# TEC_controller.net
KiCad netlist of a schematic drawn in Altium Designer
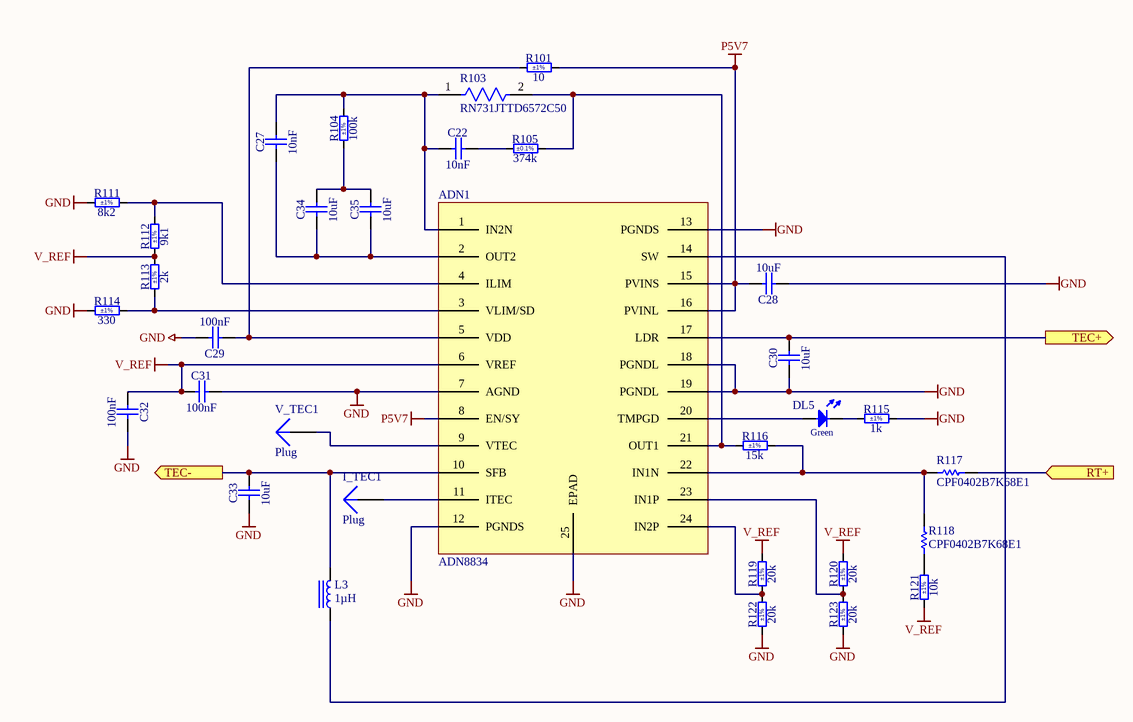
[diagram p0: TEC_controller.SchDoc]

(export (version "E")
  (design (tool "Eeschema 10.0.6"))
  (components
    (comp (ref "ADN1")
      (value "ADN8834")
      (footprint "SMSC QFN-24 4x4MM")
      (description "TEC")
      (libsource (lib "VCSEL_Driver_Lib") (part "ADN8834"))
    )
    (comp (ref "C22")
      (value "10nF")
      (footprint "CAPC1005X55N")
      (description "Non-polarised capacitor")
      (fields
        (field (name "PART NUMBER") "CC0402_10NF_16V_10%_X7R")
        (field (name "VOLTAGE") "16V")
        (field (name "AUTHOR") "CERN DEM JLC")
      )
      (libsource (lib "Capacitors") (part "Capacitor - non polarized"))
    )
    (comp (ref "C27")
      (value "10nF")
      (footprint "CAPC1005X55N")
      (description "Non-polarised capacitor")
      (fields
        (field (name "PART NUMBER") "CC0402_10NF_16V_10%_X7R")
        (field (name "VOLTAGE") "16V")
        (field (name "AUTHOR") "CERN DEM JLC")
      )
      (libsource (lib "Capacitors") (part "Capacitor - non polarized"))
    )
    (comp (ref "C28")
      (value "10uF")
      (footprint "CAPC1005X70N")
      (description "Non-polarised capacitor")
      (fields
        (field (name "PART NUMBER") "CC0402_10UF_6.3V_20%_X5R")
        (field (name "VOLTAGE") "6.3V")
        (field (name "AUTHOR") "CERN DEM JLC")
      )
      (libsource (lib "Capacitors") (part "Capacitor - non polarized"))
    )
    (comp (ref "C29")
      (value "100nF")
      (footprint "CAPC1005X55N")
      (description "Non-polarised capacitor")
      (fields
        (field (name "PART NUMBER") "CC0402_100NF_16V_10%_X7R")
        (field (name "VOLTAGE") "16V")
        (field (name "AUTHOR") "CERN DEM JLC")
      )
      (libsource (lib "Capacitors") (part "Capacitor - non polarized"))
    )
    (comp (ref "C30")
      (value "10uF")
      (footprint "CAPC1005X70N")
      (description "Non-polarised capacitor")
      (fields
        (field (name "PART NUMBER") "CC0402_10UF_6.3V_20%_X5R")
        (field (name "VOLTAGE") "6.3V")
        (field (name "AUTHOR") "CERN DEM JLC")
      )
      (libsource (lib "Capacitors") (part "Capacitor - non polarized"))
    )
    (comp (ref "C31")
      (value "100nF")
      (footprint "CAPC1005X55N")
      (description "Non-polarised capacitor")
      (fields
        (field (name "PART NUMBER") "CC0402_100NF_16V_10%_X7R")
        (field (name "VOLTAGE") "16V")
        (field (name "AUTHOR") "CERN DEM JLC")
      )
      (libsource (lib "Capacitors") (part "Capacitor - non polarized"))
    )
    (comp (ref "C32")
      (value "100nF")
      (footprint "CAPC1005X55N")
      (description "Non-polarised capacitor")
      (fields
        (field (name "PART NUMBER") "CC0402_100NF_16V_10%_X7R")
        (field (name "VOLTAGE") "16V")
        (field (name "AUTHOR") "CERN DEM JLC")
      )
      (libsource (lib "Capacitors") (part "Capacitor - non polarized"))
    )
    (comp (ref "C33")
      (value "10uF")
      (footprint "CAPC1005X70N")
      (description "Non-polarised capacitor")
      (fields
        (field (name "PART NUMBER") "CC0402_10UF_6.3V_20%_X5R")
        (field (name "VOLTAGE") "6.3V")
        (field (name "AUTHOR") "CERN DEM JLC")
      )
      (libsource (lib "Capacitors") (part "Capacitor - non polarized"))
    )
    (comp (ref "C34")
      (value "10uF")
      (footprint "CAPC1608X80N")
      (description "Non-polarised capacitor")
      (fields
        (field (name "PART NUMBER") "CC0603_10UF_16V_20%_X5R")
        (field (name "VOLTAGE") "16V")
        (field (name "AUTHOR") "CERN DEM MR")
      )
      (libsource (lib "Capacitors") (part "Capacitor - non polarized"))
    )
    (comp (ref "C35")
      (value "10uF")
      (footprint "CAPC1608X80N")
      (description "Non-polarised capacitor")
      (fields
        (field (name "PART NUMBER") "CC0603_10UF_16V_20%_X5R")
        (field (name "VOLTAGE") "16V")
        (field (name "AUTHOR") "CERN DEM MR")
      )
      (libsource (lib "Capacitors") (part "Capacitor - non polarized"))
    )
    (comp (ref "DL5")
      (value "Green")
      (footprint "LED_OSRAM_LGL29K")
      (description "LED Green 1C 2A")
      (fields
        (field (name "PART NUMBER") "LED_OSRAM_LG L29K-G2J1-24-Z")
        (field (name "MANUFACTURER") "OSRAM")
        (field (name "AUTHOR") "CERN DEM JLC")
      )
      (libsource (lib "ICs And Semiconductors") (part "LED Green 1C 2A"))
    )
    (comp (ref "I_TEC1")
      (value "Plug")
      (footprint "PIN1")
      (fields (field (name "PUBLISHER") "Altium Limited"))
      (libsource (lib "Miscellaneous Connectors") (part "Plug"))
    )
    (comp (ref "L3")
      (value "1µH")
      (footprint "IND 0806_2016")
      (description "FIXED IND 1UH 1.7A 107MOHM SMD")
      (fields
        (field (name "PART NUMBER") "SDED20161T-1R0MS")
        (field (name "MANUFACTURER") "Delta Electronics/Cyntec")
      )
      (libsource (lib "Celestial Altium Library - altium_library") (part "Inductor"))
    )
    (comp (ref "R101")
      (value "10")
      (footprint "RESC1005X40N")
      (description "Resistor - 1%")
      (fields
        (field (name "TOLERANCE") "±1%")
        (field (name "PART NUMBER") "R0402_10R_1%_0.0625W_200PPM")
        (field (name "POWER") "0.0625W")
        (field (name "AUTHOR") "CERN DEM JLC")
      )
      (libsource (lib "Resistors") (part "Resistor - 1%"))
    )
    (comp (ref "R103")
      (value "RN731JTTD6572C50")
      (footprint "FP-RN731J-IPC_B")
      (description "65.7kΩ ±0.25% 0.063W, 1/16W Chip Resistor 0603 (1608 Metric) Moisture Resistant Thin Film")
      (fields (field (name "TOLERANCE") "0.25%"))
      (libsource (lib "Altium Content Vault") (part "1029c3af85768c4190bb7ad29bc67b5"))
    )
    (comp (ref "R104")
      (value "100k")
      (footprint "RESC1005X40N")
      (description "Resistor - 1%")
      (fields
        (field (name "TOLERANCE") "±1%")
        (field (name "PART NUMBER") "R0402_100K_1%_0.0625W_100PPM")
        (field (name "POWER") "0.0625W")
        (field (name "AUTHOR") "CERN DEM JLC")
      )
      (libsource (lib "Resistors") (part "Resistor - 1%"))
    )
    (comp (ref "R105")
      (value "374k")
      (footprint "RESC1608X55N")
      (description "Resistor - 0.1%")
      (fields
        (field (name "TOLERANCE") "±0.1%")
        (field (name "PART NUMBER") "R0603_374K_0.1%_0.063W_25PPM")
        (field (name "POWER") "0.063W")
        (field (name "AUTHOR") "CERN DEM JLC")
      )
      (libsource (lib "Resistors") (part "Resistor - 0.1%"))
    )
    (comp (ref "R111")
      (value "8k2")
      (footprint "RESC1005X40N")
      (description "Resistor - 1%")
      (fields
        (field (name "TOLERANCE") "±1%")
        (field (name "PART NUMBER") "R0402_8K2_1%_0.0625W_100PPM")
        (field (name "POWER") "0.0625W")
        (field (name "AUTHOR") "CERN DEM JLC")
      )
      (libsource (lib "Resistors") (part "Resistor - 1%"))
    )
    (comp (ref "R112")
      (value "9k1")
      (footprint "RESC1005X40N")
      (description "Resistor - 1%")
      (fields
        (field (name "TOLERANCE") "±1%")
        (field (name "PART NUMBER") "R0402_9K1_1%_0.0625W_100PPM")
        (field (name "POWER") "0.0625W")
        (field (name "AUTHOR") "CERN DEM JLC")
      )
      (libsource (lib "Resistors") (part "Resistor - 1%"))
    )
    (comp (ref "R113")
      (value "2k")
      (footprint "RESC1005X40N")
      (description "Resistor - 1%")
      (fields
        (field (name "TOLERANCE") "±1%")
        (field (name "PART NUMBER") "R0402_2K_1%_0.0625W_100PPM")
        (field (name "POWER") "0.0625W")
        (field (name "AUTHOR") "CERN DEM JLC")
      )
      (libsource (lib "Resistors") (part "Resistor - 1%"))
    )
    (comp (ref "R114")
      (value "330")
      (footprint "RESC1005X40N")
      (description "Resistor - 1%")
      (fields
        (field (name "TOLERANCE") "±1%")
        (field (name "PART NUMBER") "R0402_330R_1%_0.0625W_100PPM")
        (field (name "POWER") "0.0625W")
        (field (name "AUTHOR") "CERN DEM JLC")
      )
      (libsource (lib "Resistors") (part "Resistor - 1%"))
    )
    (comp (ref "R115")
      (value "1k")
      (footprint "RESC1005X40N")
      (description "Resistor - 1%")
      (fields
        (field (name "TOLERANCE") "±1%")
        (field (name "PART NUMBER") "R0402_1K_1%_0.0625W_100PPM")
        (field (name "POWER") "0.0625W")
        (field (name "AUTHOR") "CERN DEM JLC")
      )
      (libsource (lib "Resistors") (part "Resistor - 1%"))
    )
    (comp (ref "R116")
      (value "15k")
      (footprint "RESC1005X40N")
      (description "Resistor - 1%")
      (fields
        (field (name "TOLERANCE") "±1%")
        (field (name "PART NUMBER") "R0402_15K_1%_0.0625W_100PPM")
        (field (name "POWER") "0.0625W")
        (field (name "AUTHOR") "CERN DEM JMW")
      )
      (libsource (lib "Resistors") (part "Resistor - 1%"))
    )
    (comp (ref "R117")
      (value "CPF0402B7K68E1")
      (footprint "RESC1005X35X20NL05T10")
      (fields (field (name "MANUFACTURER") "TE Connectivity / AMP"))
      (libsource (lib "Altium Content Vault") (part "RES"))
    )
    (comp (ref "R118")
      (value "CPF0402B7K68E1")
      (footprint "RESC1005X35X20NL05T10")
      (fields (field (name "MANUFACTURER") "TE Connectivity / AMP"))
      (libsource (lib "Altium Content Vault") (part "RES"))
    )
    (comp (ref "R119")
      (value "20k")
      (footprint "RESC1005X40N")
      (description "Resistor - 1%")
      (fields
        (field (name "TOLERANCE") "±1%")
        (field (name "PART NUMBER") "R0402_20K_1%_0.0625W_100PPM")
        (field (name "POWER") "0.0625W")
        (field (name "AUTHOR") "CERN DEM JLC")
      )
      (libsource (lib "Resistors") (part "Resistor - 1%"))
    )
    (comp (ref "R120")
      (value "20k")
      (footprint "RESC1005X40N")
      (description "Resistor - 1%")
      (fields
        (field (name "TOLERANCE") "±1%")
        (field (name "PART NUMBER") "R0402_20K_1%_0.0625W_100PPM")
        (field (name "POWER") "0.0625W")
        (field (name "AUTHOR") "CERN DEM JLC")
      )
      (libsource (lib "Resistors") (part "Resistor - 1%"))
    )
    (comp (ref "R121")
      (value "10k")
      (footprint "RESC1005X40N")
      (description "Resistor - 1%")
      (fields
        (field (name "TOLERANCE") "±1%")
        (field (name "PART NUMBER") "R0402_10K_1%_0.0625W_100PPM")
        (field (name "POWER") "0.0625W")
        (field (name "AUTHOR") "CERN DEM JLC")
      )
      (libsource (lib "Resistors") (part "Resistor - 1%"))
    )
    (comp (ref "R122")
      (value "20k")
      (footprint "RESC1005X40N")
      (description "Resistor - 1%")
      (fields
        (field (name "TOLERANCE") "±1%")
        (field (name "PART NUMBER") "R0402_20K_1%_0.0625W_100PPM")
        (field (name "POWER") "0.0625W")
        (field (name "AUTHOR") "CERN DEM JLC")
      )
      (libsource (lib "Resistors") (part "Resistor - 1%"))
    )
    (comp (ref "R123")
      (value "20k")
      (footprint "RESC1005X40N")
      (description "Resistor - 1%")
      (fields
        (field (name "TOLERANCE") "±1%")
        (field (name "PART NUMBER") "R0402_20K_1%_0.0625W_100PPM")
        (field (name "POWER") "0.0625W")
        (field (name "AUTHOR") "CERN DEM JLC")
      )
      (libsource (lib "Resistors") (part "Resistor - 1%"))
    )
    (comp (ref "V_TEC1")
      (value "Plug")
      (footprint "PIN1")
      (fields (field (name "PUBLISHER") "Altium Limited"))
      (libsource (lib "Miscellaneous Connectors") (part "Plug"))
    )
  )
  (nets
    (net (code "1") (name "/RT+") (class "Default")
      (node (ref "R117") (pin "2") (pinfunction "2_2") (pintype "passive"))
    )
    (net (code "2") (name "/TEC+") (class "Default")
      (node (ref "ADN1") (pin "17") (pinfunction "LDR_17") (pintype "passive"))
      (node (ref "C30") (pin "2") (pinfunction "2_2") (pintype "passive"))
    )
    (net (code "3") (name "/TEC-") (class "Default")
      (node (ref "ADN1") (pin "10") (pinfunction "SFB_10") (pintype "passive"))
      (node (ref "C33") (pin "2") (pinfunction "2_2") (pintype "passive"))
      (node (ref "L3") (pin "2") (pinfunction "2_2") (pintype "passive"))
    )
    (net (code "4") (name "GND") (class "Default")
      (node (ref "ADN1") (pin "12") (pinfunction "PGNDS_12") (pintype "passive"))
      (node (ref "ADN1") (pin "13") (pinfunction "PGNDS_13") (pintype "passive"))
      (node (ref "ADN1") (pin "18") (pinfunction "PGNDL_18") (pintype "passive"))
      (node (ref "ADN1") (pin "19") (pinfunction "PGNDL_19") (pintype "passive"))
      (node (ref "ADN1") (pin "25") (pinfunction "EPAD_25") (pintype "passive"))
      (node (ref "ADN1") (pin "7") (pinfunction "AGND_7") (pintype "passive"))
      (node (ref "C28") (pin "1") (pinfunction "1_1") (pintype "passive"))
      (node (ref "C29") (pin "2") (pinfunction "2_2") (pintype "passive"))
      (node (ref "C30") (pin "1") (pinfunction "1_1") (pintype "passive"))
      (node (ref "C31") (pin "2") (pinfunction "2_2") (pintype "passive"))
      (node (ref "C32") (pin "2") (pinfunction "2_2") (pintype "passive"))
      (node (ref "C33") (pin "1") (pinfunction "1_1") (pintype "passive"))
      (node (ref "R111") (pin "1") (pinfunction "1_1") (pintype "passive"))
      (node (ref "R114") (pin "1") (pinfunction "1_1") (pintype "passive"))
      (node (ref "R115") (pin "2") (pinfunction "2_2") (pintype "passive"))
      (node (ref "R122") (pin "1") (pinfunction "1_1") (pintype "passive"))
      (node (ref "R123") (pin "1") (pinfunction "1_1") (pintype "passive"))
    )
    (net (code "5") (name "Net-(ADN1-ILIM)") (class "Default")
      (node (ref "ADN1") (pin "4") (pinfunction "ILIM_4") (pintype "passive"))
      (node (ref "R111") (pin "2") (pinfunction "2_2") (pintype "passive"))
      (node (ref "R112") (pin "2") (pinfunction "2_2") (pintype "passive"))
    )
    (net (code "6") (name "Net-(ADN1-IN1N)") (class "Default")
      (node (ref "ADN1") (pin "22") (pinfunction "IN1N_22") (pintype "passive"))
      (node (ref "R116") (pin "2") (pinfunction "2_2") (pintype "passive"))
      (node (ref "R117") (pin "1") (pinfunction "1_1") (pintype "passive"))
      (node (ref "R118") (pin "2") (pinfunction "2_2") (pintype "passive"))
    )
    (net (code "7") (name "Net-(ADN1-IN1P)") (class "Default")
      (node (ref "ADN1") (pin "23") (pinfunction "IN1P_23") (pintype "passive"))
      (node (ref "R120") (pin "1") (pinfunction "1_1") (pintype "passive"))
      (node (ref "R123") (pin "2") (pinfunction "2_2") (pintype "passive"))
    )
    (net (code "8") (name "Net-(ADN1-IN2N)") (class "Default")
      (node (ref "ADN1") (pin "1") (pinfunction "IN2N_1") (pintype "passive"))
      (node (ref "C22") (pin "1") (pinfunction "1_1") (pintype "passive"))
      (node (ref "C27") (pin "2") (pinfunction "2_2") (pintype "passive"))
      (node (ref "R103") (pin "1") (pinfunction "1_1") (pintype "passive"))
      (node (ref "R104") (pin "2") (pinfunction "2_2") (pintype "passive"))
    )
    (net (code "9") (name "Net-(ADN1-IN2P)") (class "Default")
      (node (ref "ADN1") (pin "24") (pinfunction "IN2P_24") (pintype "passive"))
      (node (ref "R119") (pin "1") (pinfunction "1_1") (pintype "passive"))
      (node (ref "R122") (pin "2") (pinfunction "2_2") (pintype "passive"))
    )
    (net (code "10") (name "Net-(ADN1-ITEC)") (class "Default")
      (node (ref "ADN1") (pin "11") (pinfunction "ITEC_11") (pintype "passive"))
      (node (ref "I_TEC1") (pin "1") (pinfunction "1_1") (pintype "passive"))
    )
    (net (code "11") (name "Net-(ADN1-OUT1)") (class "Default")
      (node (ref "ADN1") (pin "21") (pinfunction "OUT1_21") (pintype "passive"))
      (node (ref "R103") (pin "2") (pinfunction "2_2") (pintype "passive"))
      (node (ref "R105") (pin "2") (pinfunction "2_2") (pintype "passive"))
      (node (ref "R116") (pin "1") (pinfunction "1_1") (pintype "passive"))
    )
    (net (code "12") (name "Net-(ADN1-OUT2)") (class "Default")
      (node (ref "ADN1") (pin "2") (pinfunction "OUT2_2") (pintype "passive"))
      (node (ref "C27") (pin "1") (pinfunction "1_1") (pintype "passive"))
      (node (ref "C34") (pin "1") (pinfunction "1_1") (pintype "passive"))
      (node (ref "C35") (pin "1") (pinfunction "1_1") (pintype "passive"))
    )
    (net (code "13") (name "Net-(ADN1-SW)") (class "Default")
      (node (ref "ADN1") (pin "14") (pinfunction "SW_14") (pintype "passive"))
      (node (ref "L3") (pin "1") (pinfunction "1_1") (pintype "passive"))
    )
    (net (code "14") (name "Net-(ADN1-TMPGD)") (class "Default")
      (node (ref "ADN1") (pin "20") (pinfunction "TMPGD_20") (pintype "passive"))
      (node (ref "DL5") (pin "2") (pinfunction "A_2") (pintype "passive"))
    )
    (net (code "15") (name "Net-(ADN1-VDD)") (class "Default")
      (node (ref "ADN1") (pin "5") (pinfunction "VDD_5") (pintype "passive"))
      (node (ref "C29") (pin "1") (pinfunction "1_1") (pintype "passive"))
      (node (ref "R101") (pin "1") (pinfunction "1_1") (pintype "passive"))
    )
    (net (code "16") (name "Net-(ADN1-VLIM{slash}SD)") (class "Default")
      (node (ref "ADN1") (pin "3") (pinfunction "VLIM/SD_3") (pintype "passive"))
      (node (ref "R113") (pin "1") (pinfunction "1_1") (pintype "passive"))
      (node (ref "R114") (pin "2") (pinfunction "2_2") (pintype "passive"))
    )
    (net (code "17") (name "Net-(ADN1-VTEC)") (class "Default")
      (node (ref "ADN1") (pin "9") (pinfunction "VTEC_9") (pintype "passive"))
      (node (ref "V_TEC1") (pin "1") (pinfunction "1_1") (pintype "passive"))
    )
    (net (code "18") (name "Net-(C22-Pad2)") (class "Default")
      (node (ref "C22") (pin "2") (pinfunction "2_2") (pintype "passive"))
      (node (ref "R105") (pin "1") (pinfunction "1_1") (pintype "passive"))
    )
    (net (code "19") (name "Net-(C34-Pad2)") (class "Default")
      (node (ref "C34") (pin "2") (pinfunction "2_2") (pintype "passive"))
      (node (ref "C35") (pin "2") (pinfunction "2_2") (pintype "passive"))
      (node (ref "R104") (pin "1") (pinfunction "1_1") (pintype "passive"))
    )
    (net (code "20") (name "Net-(DL5-C)") (class "Default")
      (node (ref "DL5") (pin "1") (pinfunction "C_1") (pintype "passive"))
      (node (ref "R115") (pin "1") (pinfunction "1_1") (pintype "passive"))
    )
    (net (code "21") (name "Net-(R118-Pad1)") (class "Default")
      (node (ref "R118") (pin "1") (pinfunction "1_1") (pintype "passive"))
      (node (ref "R121") (pin "2") (pinfunction "2_2") (pintype "passive"))
    )
    (net (code "22") (name "P5V7") (class "Default")
      (node (ref "ADN1") (pin "15") (pinfunction "PVINS_15") (pintype "passive"))
      (node (ref "ADN1") (pin "16") (pinfunction "PVINL_16") (pintype "passive"))
      (node (ref "ADN1") (pin "8") (pinfunction "EN/SY_8") (pintype "passive"))
      (node (ref "C28") (pin "2") (pinfunction "2_2") (pintype "passive"))
      (node (ref "R101") (pin "2") (pinfunction "2_2") (pintype "passive"))
    )
    (net (code "23") (name "V_REF") (class "Default")
      (node (ref "ADN1") (pin "6") (pinfunction "VREF_6") (pintype "passive"))
      (node (ref "C31") (pin "1") (pinfunction "1_1") (pintype "passive"))
      (node (ref "C32") (pin "1") (pinfunction "1_1") (pintype "passive"))
      (node (ref "R112") (pin "1") (pinfunction "1_1") (pintype "passive"))
      (node (ref "R113") (pin "2") (pinfunction "2_2") (pintype "passive"))
      (node (ref "R119") (pin "2") (pinfunction "2_2") (pintype "passive"))
      (node (ref "R120") (pin "2") (pinfunction "2_2") (pintype "passive"))
      (node (ref "R121") (pin "1") (pinfunction "1_1") (pintype "passive"))
    )
  )
)
